# Sensors.net
KiCad netlist of a schematic drawn in Altium Designer
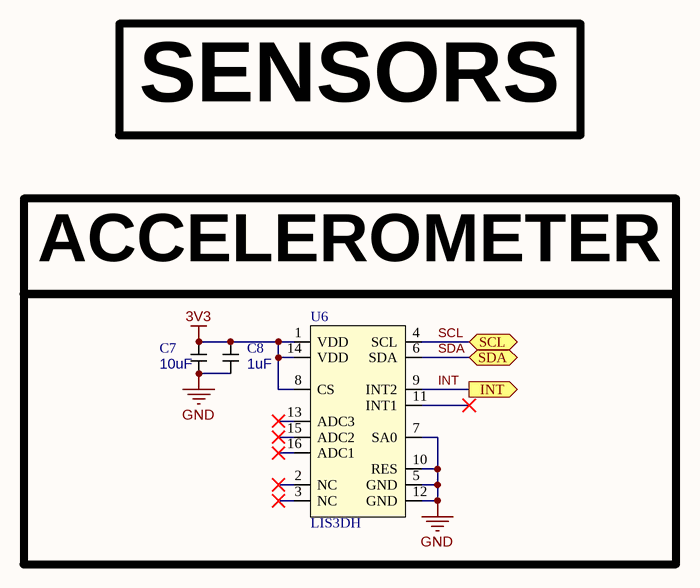
[diagram p0: Sensors.SchDoc]

(export (version "E")
  (design (tool "Eeschema 10.0.6"))
  (components
    (comp (ref "C7")
      (value "10uF")
      (footprint "CAP_0402_HIGH")
      (description "0402 Capacitor")
      (libsource (lib "smLib") (part "Capacitor_0402"))
    )
    (comp (ref "C8")
      (value "1uF")
      (footprint "CAP_0402_HIGH")
      (description "0402 Capacitor")
      (libsource (lib "smLib") (part "Capacitor_0402"))
    )
    (comp (ref "U6")
      (value "LIS3DH")
      (footprint "LIS3DH")
      (description "LIS3DH ACCEL 2-16G I2C/SPI 16LGA")
      (libsource (lib "smLib") (part "LIS3DH"))
    )
  )
  (nets
    (net (code "1") (name "/INT") (class "Default")
      (node (ref "U6") (pin "9") (pinfunction "INT2_9") (pintype "passive"))
    )
    (net (code "2") (name "/SCL") (class "Default")
      (node (ref "U6") (pin "4") (pinfunction "SCL_4") (pintype "passive"))
    )
    (net (code "3") (name "/SDA") (class "Default")
      (node (ref "U6") (pin "6") (pinfunction "SDA_6") (pintype "passive"))
    )
    (net (code "4") (name "3V3") (class "Default")
      (node (ref "C7") (pin "2") (pinfunction "2_2") (pintype "passive"))
      (node (ref "C8") (pin "2") (pinfunction "2_2") (pintype "passive"))
      (node (ref "U6") (pin "1") (pinfunction "VDD_1") (pintype "passive"))
      (node (ref "U6") (pin "14") (pinfunction "VDD_14") (pintype "passive"))
      (node (ref "U6") (pin "8") (pinfunction "CS_8") (pintype "passive"))
    )
    (net (code "5") (name "GND") (class "Default")
      (node (ref "C7") (pin "1") (pinfunction "1_1") (pintype "passive"))
      (node (ref "C8") (pin "1") (pinfunction "1_1") (pintype "passive"))
      (node (ref "U6") (pin "10") (pinfunction "RES_10") (pintype "passive"))
      (node (ref "U6") (pin "12") (pinfunction "GND_12") (pintype "passive"))
      (node (ref "U6") (pin "5") (pinfunction "GND_5") (pintype "passive"))
      (node (ref "U6") (pin "7") (pinfunction "SA0_7") (pintype "passive"))
    )
    (net (code "6") (name "unconnected-(U6-ADC1-Pad16)") (class "Default")
      (node (ref "U6") (pin "16") (pinfunction "ADC1_16") (pintype "passive+no_connect"))
    )
    (net (code "7") (name "unconnected-(U6-ADC2-Pad15)") (class "Default")
      (node (ref "U6") (pin "15") (pinfunction "ADC2_15") (pintype "passive+no_connect"))
    )
    (net (code "8") (name "unconnected-(U6-ADC3-Pad13)") (class "Default")
      (node (ref "U6") (pin "13") (pinfunction "ADC3_13") (pintype "passive+no_connect"))
    )
    (net (code "9") (name "unconnected-(U6-INT1-Pad11)") (class "Default")
      (node (ref "U6") (pin "11") (pinfunction "INT1_11") (pintype "passive+no_connect"))
    )
    (net (code "10") (name "unconnected-(U6-NC-Pad2)") (class "Default")
      (node (ref "U6") (pin "2") (pinfunction "NC_2") (pintype "passive+no_connect"))
    )
    (net (code "11") (name "unconnected-(U6-NC-Pad3)") (class "Default")
      (node (ref "U6") (pin "3") (pinfunction "NC_3") (pintype "passive+no_connect"))
    )
  )
)
